# AppleMouse.net
KiCad netlist of a schematic drawn in EAGLE
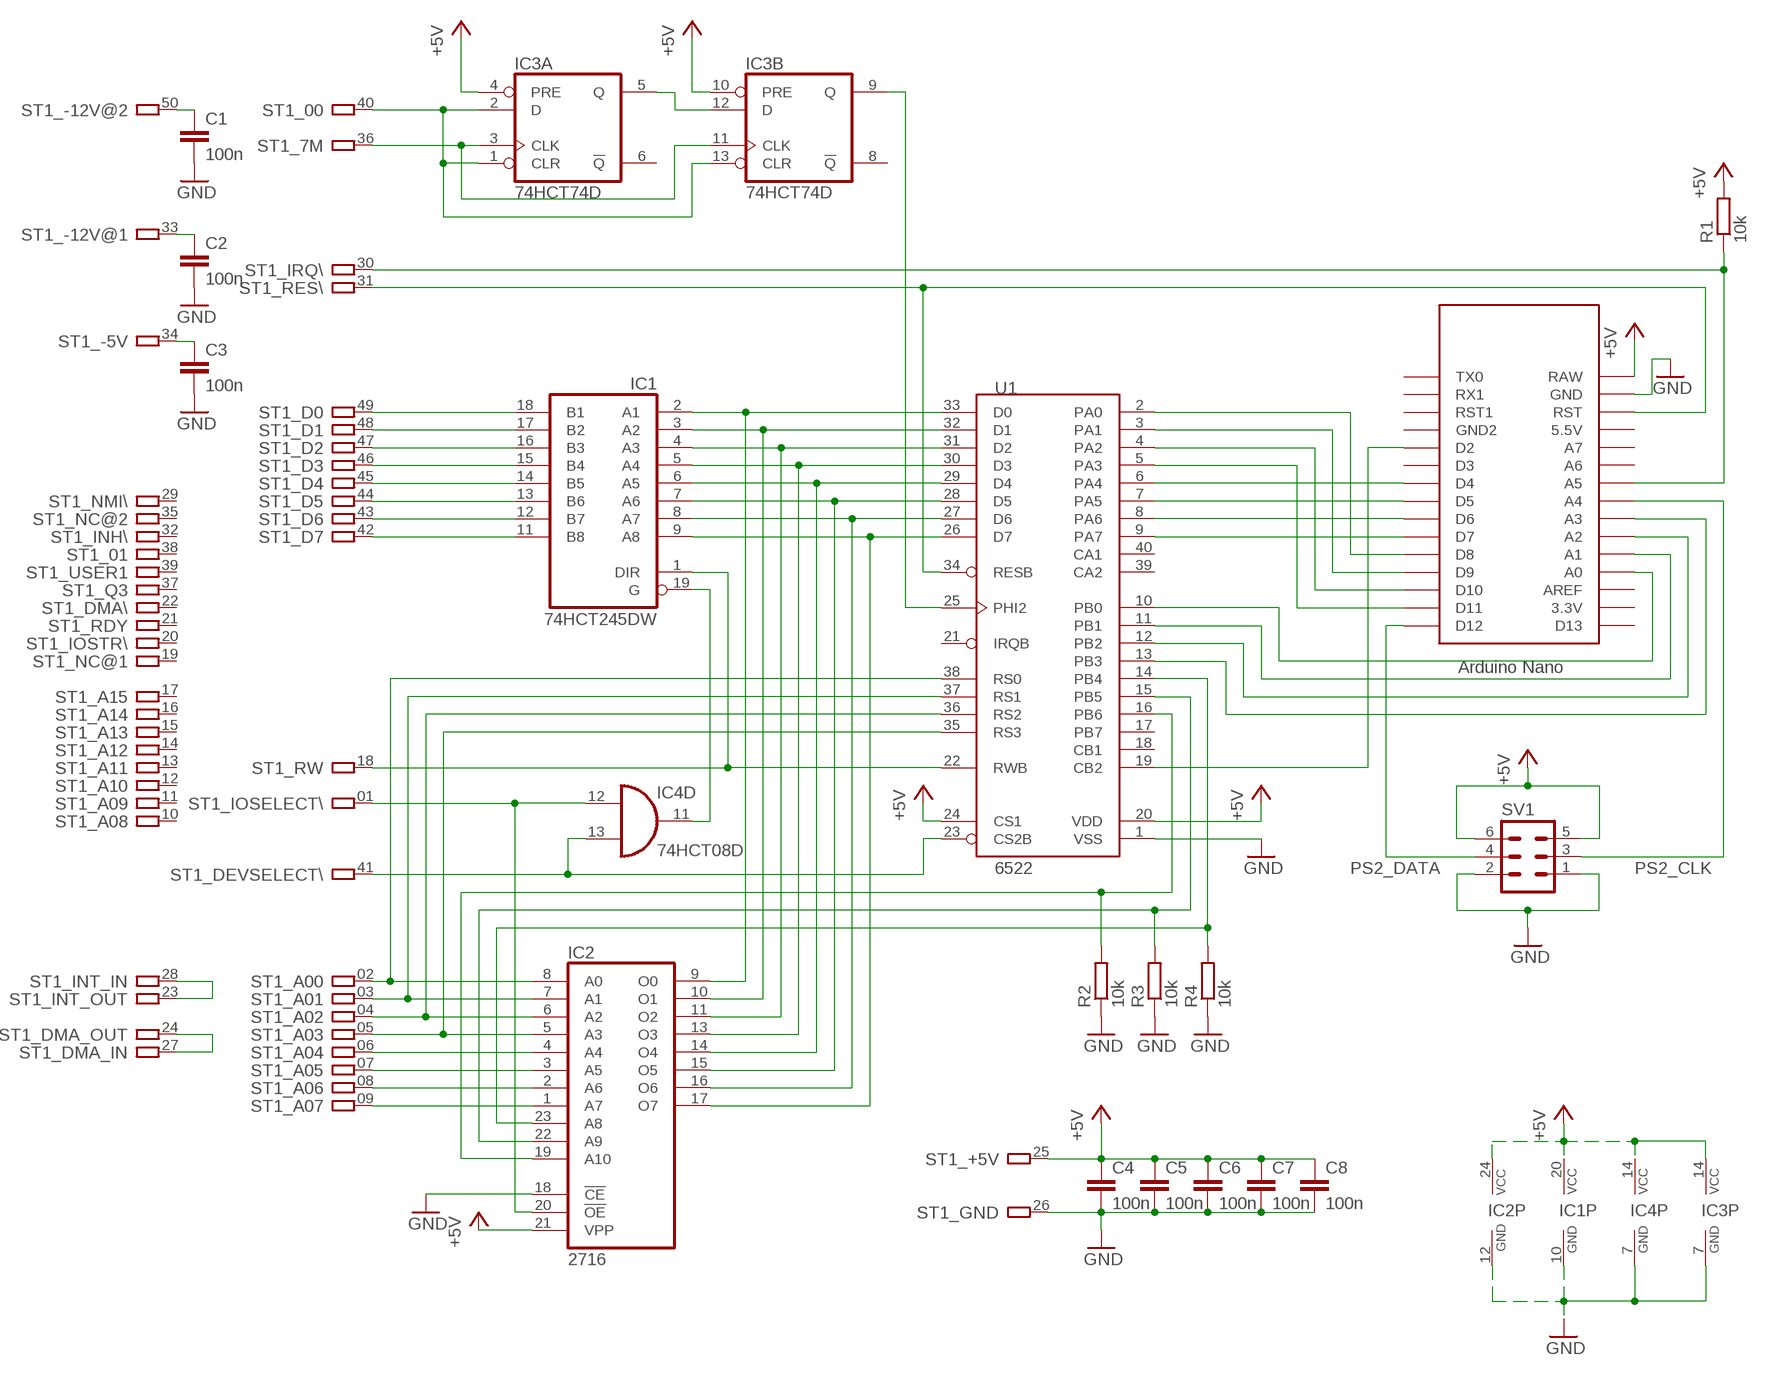
[diagram p0: schematic, sheet 1]

(export (version "E")
  (design (tool "Eeschema 10.0.6"))
  (components
    (comp (ref "C1")
      (value "100n")
      (footprint "eagle-import:C0805")
      (libsource (lib "eagle-import") (part "C-EUC0805"))
    )
    (comp (ref "C2")
      (value "100n")
      (footprint "eagle-import:C0805")
      (libsource (lib "eagle-import") (part "C-EUC0805"))
    )
    (comp (ref "C3")
      (value "100n")
      (footprint "eagle-import:C0805")
      (libsource (lib "eagle-import") (part "C-EUC0805"))
    )
    (comp (ref "C4")
      (value "100n")
      (footprint "eagle-import:C0805")
      (libsource (lib "eagle-import") (part "C-EUC0805"))
    )
    (comp (ref "C5")
      (value "100n")
      (footprint "eagle-import:C0805")
      (libsource (lib "eagle-import") (part "C-EUC0805"))
    )
    (comp (ref "C6")
      (value "100n")
      (footprint "eagle-import:C0805")
      (libsource (lib "eagle-import") (part "C-EUC0805"))
    )
    (comp (ref "C7")
      (value "100n")
      (footprint "eagle-import:C0805")
      (libsource (lib "eagle-import") (part "C-EUC0805"))
    )
    (comp (ref "C8")
      (value "100n")
      (footprint "eagle-import:C0805")
      (libsource (lib "eagle-import") (part "C-EUC0805"))
    )
    (comp (ref "IC1")
      (value "74HCT245DW")
      (footprint "eagle-import:SO20W")
      (libsource (lib "eagle-import") (part "74245DWHCT"))
    )
    (comp (ref "IC2")
      (value "2716")
      (footprint "eagle-import:DIL24")
      (libsource (lib "eagle-import") (part "2716"))
    )
    (comp (ref "IC3")
      (value "74HCT74D")
      (footprint "eagle-import:SO14")
      (libsource (lib "eagle-import") (part "7474DHCT"))
    )
    (comp (ref "IC4")
      (value "74HCT08D")
      (footprint "eagle-import:SO14")
      (libsource (lib "eagle-import") (part "7408DHCT"))
    )
    (comp (ref "R1")
      (value "10k")
      (footprint "eagle-import:R0805")
      (libsource (lib "eagle-import") (part "R-EU_R0805"))
    )
    (comp (ref "R2")
      (value "10k")
      (footprint "eagle-import:R0805")
      (libsource (lib "eagle-import") (part "R-EU_R0805"))
    )
    (comp (ref "R3")
      (value "10k")
      (footprint "eagle-import:R0805")
      (libsource (lib "eagle-import") (part "R-EU_R0805"))
    )
    (comp (ref "R4")
      (value "10k")
      (footprint "eagle-import:R0805")
      (libsource (lib "eagle-import") (part "R-EU_R0805"))
    )
    (comp (ref "ST1")
      (value "A2-50PINSLOT1-3")
      (footprint "eagle-import:A2-50PIN-SL1-3")
      (libsource (lib "eagle-import") (part "A2-50PINSLOT1-3"))
    )
    (comp (ref "SV1")
      (value "ML6")
      (footprint "eagle-import:ML6")
      (libsource (lib "eagle-import") (part "ML6"))
    )
    (comp (ref "U$1")
      (value "NANO")
      (footprint "eagle-import:NANO")
      (libsource (lib "eagle-import") (part "NANO"))
    )
    (comp (ref "U1")
      (value "6522")
      (footprint "eagle-import:DIP40")
      (libsource (lib "eagle-import") (part "W65C22DIP40"))
    )
  )
  (nets
    (net (code "1") (name "+5V") (class "Default")
      (node (ref "C4") (pin "1") (pinfunction "1_1") (pintype "passive"))
      (node (ref "C5") (pin "1") (pinfunction "1_1") (pintype "passive"))
      (node (ref "C6") (pin "1") (pinfunction "1_1") (pintype "passive"))
      (node (ref "C7") (pin "1") (pinfunction "1_1") (pintype "passive"))
      (node (ref "C8") (pin "1") (pinfunction "1_1") (pintype "passive"))
      (node (ref "IC1") (pin "20") (pinfunction "VCC_20") (pintype "power_in"))
      (node (ref "IC2") (pin "21") (pinfunction "VPP_21") (pintype "input"))
      (node (ref "IC2") (pin "24") (pinfunction "VCC_24") (pintype "power_in"))
      (node (ref "IC3") (pin "10") (pinfunction "PRE_10") (pintype "input"))
      (node (ref "IC3") (pin "14") (pinfunction "VCC_14") (pintype "power_in"))
      (node (ref "IC3") (pin "4") (pinfunction "PRE_4") (pintype "input"))
      (node (ref "IC4") (pin "14") (pinfunction "VCC_14") (pintype "power_in"))
      (node (ref "R1") (pin "2") (pinfunction "2_2") (pintype "passive"))
      (node (ref "ST1") (pin "25") (pinfunction "P_25") (pintype "bidirectional"))
      (node (ref "SV1") (pin "5") (pinfunction "5_5") (pintype "passive"))
      (node (ref "SV1") (pin "6") (pinfunction "6_6") (pintype "passive"))
      (node (ref "U$1") (pin "RAW") (pinfunction "RAW_RAW") (pintype "bidirectional"))
      (node (ref "U1") (pin "20") (pinfunction "VDD_20") (pintype "power_in"))
      (node (ref "U1") (pin "24") (pinfunction "CS1_24") (pintype "input"))
    )
    (net (code "2") (name "/PS2_CLK") (class "Default")
      (node (ref "SV1") (pin "3") (pinfunction "3_3") (pintype "passive"))
      (node (ref "U$1") (pin "A4") (pinfunction "A4_A4") (pintype "bidirectional"))
    )
    (net (code "3") (name "/PS2_DATA") (class "Default")
      (node (ref "SV1") (pin "4") (pinfunction "4_4") (pintype "passive"))
      (node (ref "U$1") (pin "D12") (pinfunction "D12_D12") (pintype "bidirectional"))
    )
    (net (code "4") (name "GND") (class "Default")
      (node (ref "C1") (pin "2") (pinfunction "2_2") (pintype "passive"))
      (node (ref "C2") (pin "2") (pinfunction "2_2") (pintype "passive"))
      (node (ref "C3") (pin "2") (pinfunction "2_2") (pintype "passive"))
      (node (ref "C4") (pin "2") (pinfunction "2_2") (pintype "passive"))
      (node (ref "C5") (pin "2") (pinfunction "2_2") (pintype "passive"))
      (node (ref "C6") (pin "2") (pinfunction "2_2") (pintype "passive"))
      (node (ref "C7") (pin "2") (pinfunction "2_2") (pintype "passive"))
      (node (ref "C8") (pin "2") (pinfunction "2_2") (pintype "passive"))
      (node (ref "IC1") (pin "10") (pinfunction "GND_10") (pintype "power_in"))
      (node (ref "IC2") (pin "12") (pinfunction "GND_12") (pintype "power_in"))
      (node (ref "IC2") (pin "18") (pinfunction "~{CE}_18") (pintype "input"))
      (node (ref "IC3") (pin "7") (pinfunction "GND_7") (pintype "power_in"))
      (node (ref "IC4") (pin "7") (pinfunction "GND_7") (pintype "power_in"))
      (node (ref "R2") (pin "1") (pinfunction "1_1") (pintype "passive"))
      (node (ref "R3") (pin "1") (pinfunction "1_1") (pintype "passive"))
      (node (ref "R4") (pin "1") (pinfunction "1_1") (pintype "passive"))
      (node (ref "ST1") (pin "26") (pinfunction "P_26") (pintype "bidirectional"))
      (node (ref "SV1") (pin "1") (pinfunction "1_1") (pintype "passive"))
      (node (ref "SV1") (pin "2") (pinfunction "2_2") (pintype "passive"))
      (node (ref "U$1") (pin "GND") (pinfunction "GND_GND") (pintype "bidirectional"))
      (node (ref "U1") (pin "1") (pinfunction "VSS_1") (pintype "power_in"))
    )
    (net (code "5") (name "Net-(IC1A-A1)") (class "Default")
      (node (ref "IC1") (pin "2") (pinfunction "A1_2") (pintype "bidirectional"))
      (node (ref "IC2") (pin "9") (pinfunction "O0_9") (pintype "tri_state"))
      (node (ref "U1") (pin "33") (pinfunction "D0_33") (pintype "bidirectional"))
    )
    (net (code "6") (name "Net-(IC1A-A2)") (class "Default")
      (node (ref "IC1") (pin "3") (pinfunction "A2_3") (pintype "bidirectional"))
      (node (ref "IC2") (pin "10") (pinfunction "O1_10") (pintype "tri_state"))
      (node (ref "U1") (pin "32") (pinfunction "D1_32") (pintype "bidirectional"))
    )
    (net (code "7") (name "Net-(IC1A-A3)") (class "Default")
      (node (ref "IC1") (pin "4") (pinfunction "A3_4") (pintype "bidirectional"))
      (node (ref "IC2") (pin "11") (pinfunction "O2_11") (pintype "tri_state"))
      (node (ref "U1") (pin "31") (pinfunction "D2_31") (pintype "bidirectional"))
    )
    (net (code "8") (name "Net-(IC1A-A4)") (class "Default")
      (node (ref "IC1") (pin "5") (pinfunction "A4_5") (pintype "bidirectional"))
      (node (ref "IC2") (pin "13") (pinfunction "O3_13") (pintype "tri_state"))
      (node (ref "U1") (pin "30") (pinfunction "D3_30") (pintype "bidirectional"))
    )
    (net (code "9") (name "Net-(IC1A-A5)") (class "Default")
      (node (ref "IC1") (pin "6") (pinfunction "A5_6") (pintype "bidirectional"))
      (node (ref "IC2") (pin "14") (pinfunction "O4_14") (pintype "tri_state"))
      (node (ref "U1") (pin "29") (pinfunction "D4_29") (pintype "bidirectional"))
    )
    (net (code "10") (name "Net-(IC1A-A6)") (class "Default")
      (node (ref "IC1") (pin "7") (pinfunction "A6_7") (pintype "bidirectional"))
      (node (ref "IC2") (pin "15") (pinfunction "O5_15") (pintype "tri_state"))
      (node (ref "U1") (pin "28") (pinfunction "D5_28") (pintype "bidirectional"))
    )
    (net (code "11") (name "Net-(IC1A-A7)") (class "Default")
      (node (ref "IC1") (pin "8") (pinfunction "A7_8") (pintype "bidirectional"))
      (node (ref "IC2") (pin "16") (pinfunction "O6_16") (pintype "tri_state"))
      (node (ref "U1") (pin "27") (pinfunction "D6_27") (pintype "bidirectional"))
    )
    (net (code "12") (name "Net-(IC1A-A8)") (class "Default")
      (node (ref "IC1") (pin "9") (pinfunction "A8_9") (pintype "bidirectional"))
      (node (ref "IC2") (pin "17") (pinfunction "O7_17") (pintype "tri_state"))
      (node (ref "U1") (pin "26") (pinfunction "D7_26") (pintype "bidirectional"))
    )
    (net (code "13") (name "Net-(IC1A-B1)") (class "Default")
      (node (ref "IC1") (pin "18") (pinfunction "B1_18") (pintype "bidirectional"))
      (node (ref "ST1") (pin "49") (pinfunction "P_49") (pintype "bidirectional"))
    )
    (net (code "14") (name "Net-(IC1A-B2)") (class "Default")
      (node (ref "IC1") (pin "17") (pinfunction "B2_17") (pintype "bidirectional"))
      (node (ref "ST1") (pin "48") (pinfunction "P_48") (pintype "bidirectional"))
    )
    (net (code "15") (name "Net-(IC1A-B3)") (class "Default")
      (node (ref "IC1") (pin "16") (pinfunction "B3_16") (pintype "bidirectional"))
      (node (ref "ST1") (pin "47") (pinfunction "P_47") (pintype "bidirectional"))
    )
    (net (code "16") (name "Net-(IC1A-B4)") (class "Default")
      (node (ref "IC1") (pin "15") (pinfunction "B4_15") (pintype "bidirectional"))
      (node (ref "ST1") (pin "46") (pinfunction "P_46") (pintype "bidirectional"))
    )
    (net (code "17") (name "Net-(IC1A-B5)") (class "Default")
      (node (ref "IC1") (pin "14") (pinfunction "B5_14") (pintype "bidirectional"))
      (node (ref "ST1") (pin "45") (pinfunction "P_45") (pintype "bidirectional"))
    )
    (net (code "18") (name "Net-(IC1A-B6)") (class "Default")
      (node (ref "IC1") (pin "13") (pinfunction "B6_13") (pintype "bidirectional"))
      (node (ref "ST1") (pin "44") (pinfunction "P_44") (pintype "bidirectional"))
    )
    (net (code "19") (name "Net-(IC1A-B7)") (class "Default")
      (node (ref "IC1") (pin "12") (pinfunction "B7_12") (pintype "bidirectional"))
      (node (ref "ST1") (pin "43") (pinfunction "P_43") (pintype "bidirectional"))
    )
    (net (code "20") (name "Net-(IC1A-B8)") (class "Default")
      (node (ref "IC1") (pin "11") (pinfunction "B8_11") (pintype "bidirectional"))
      (node (ref "ST1") (pin "42") (pinfunction "P_42") (pintype "bidirectional"))
    )
    (net (code "21") (name "Net-(IC1A-DIR)") (class "Default")
      (node (ref "IC1") (pin "1") (pinfunction "DIR_1") (pintype "input"))
      (node (ref "ST1") (pin "18") (pinfunction "P_18") (pintype "bidirectional"))
      (node (ref "U1") (pin "22") (pinfunction "RWB_22") (pintype "input"))
    )
    (net (code "22") (name "Net-(IC1A-G)") (class "Default")
      (node (ref "IC1") (pin "19") (pinfunction "G_19") (pintype "input"))
      (node (ref "IC4") (pin "11") (pinfunction "O_11") (pintype "output"))
    )
    (net (code "23") (name "Net-(IC2A-A0)") (class "Default")
      (node (ref "IC2") (pin "8") (pinfunction "A0_8") (pintype "input"))
      (node (ref "ST1") (pin "02") (pinfunction "P_02") (pintype "bidirectional"))
      (node (ref "U1") (pin "38") (pinfunction "RS0_38") (pintype "input"))
    )
    (net (code "24") (name "Net-(IC2A-A1)") (class "Default")
      (node (ref "IC2") (pin "7") (pinfunction "A1_7") (pintype "input"))
      (node (ref "ST1") (pin "03") (pinfunction "P_03") (pintype "bidirectional"))
      (node (ref "U1") (pin "37") (pinfunction "RS1_37") (pintype "input"))
    )
    (net (code "25") (name "Net-(IC2A-A2)") (class "Default")
      (node (ref "IC2") (pin "6") (pinfunction "A2_6") (pintype "input"))
      (node (ref "ST1") (pin "04") (pinfunction "P_04") (pintype "bidirectional"))
      (node (ref "U1") (pin "36") (pinfunction "RS2_36") (pintype "input"))
    )
    (net (code "26") (name "Net-(IC2A-A3)") (class "Default")
      (node (ref "IC2") (pin "5") (pinfunction "A3_5") (pintype "input"))
      (node (ref "ST1") (pin "05") (pinfunction "P_05") (pintype "bidirectional"))
      (node (ref "U1") (pin "35") (pinfunction "RS3_35") (pintype "input"))
    )
    (net (code "27") (name "Net-(IC2A-A4)") (class "Default")
      (node (ref "IC2") (pin "4") (pinfunction "A4_4") (pintype "input"))
      (node (ref "ST1") (pin "06") (pinfunction "P_06") (pintype "bidirectional"))
    )
    (net (code "28") (name "Net-(IC2A-A5)") (class "Default")
      (node (ref "IC2") (pin "3") (pinfunction "A5_3") (pintype "input"))
      (node (ref "ST1") (pin "07") (pinfunction "P_07") (pintype "bidirectional"))
    )
    (net (code "29") (name "Net-(IC2A-A6)") (class "Default")
      (node (ref "IC2") (pin "2") (pinfunction "A6_2") (pintype "input"))
      (node (ref "ST1") (pin "08") (pinfunction "P_08") (pintype "bidirectional"))
    )
    (net (code "30") (name "Net-(IC2A-A7)") (class "Default")
      (node (ref "IC2") (pin "1") (pinfunction "A7_1") (pintype "input"))
      (node (ref "ST1") (pin "09") (pinfunction "P_09") (pintype "bidirectional"))
    )
    (net (code "31") (name "Net-(IC2A-A8)") (class "Default")
      (node (ref "IC2") (pin "23") (pinfunction "A8_23") (pintype "input"))
      (node (ref "R4") (pin "2") (pinfunction "2_2") (pintype "passive"))
      (node (ref "U1") (pin "14") (pinfunction "PB4_14") (pintype "bidirectional"))
    )
    (net (code "32") (name "Net-(IC2A-A9)") (class "Default")
      (node (ref "IC2") (pin "22") (pinfunction "A9_22") (pintype "input"))
      (node (ref "R3") (pin "2") (pinfunction "2_2") (pintype "passive"))
      (node (ref "U1") (pin "15") (pinfunction "PB5_15") (pintype "bidirectional"))
    )
    (net (code "33") (name "Net-(IC2A-A10)") (class "Default")
      (node (ref "IC2") (pin "19") (pinfunction "A10_19") (pintype "input"))
      (node (ref "R2") (pin "2") (pinfunction "2_2") (pintype "passive"))
      (node (ref "U1") (pin "16") (pinfunction "PB6_16") (pintype "bidirectional"))
    )
    (net (code "34") (name "Net-(IC2A-~{OE})") (class "Default")
      (node (ref "IC2") (pin "20") (pinfunction "~{OE}_20") (pintype "input"))
      (node (ref "IC4") (pin "12") (pinfunction "I0_12") (pintype "input"))
      (node (ref "ST1") (pin "01") (pinfunction "P_01") (pintype "bidirectional"))
    )
    (net (code "35") (name "Net-(IC3A-CLK)") (class "Default")
      (node (ref "IC3") (pin "11") (pinfunction "CLK_11") (pintype "input"))
      (node (ref "IC3") (pin "3") (pinfunction "CLK_3") (pintype "input"))
      (node (ref "ST1") (pin "36") (pinfunction "P_36") (pintype "bidirectional"))
    )
    (net (code "36") (name "Net-(IC3A-CLR)") (class "Default")
      (node (ref "IC3") (pin "1") (pinfunction "CLR_1") (pintype "input"))
      (node (ref "IC3") (pin "13") (pinfunction "CLR_13") (pintype "input"))
      (node (ref "IC3") (pin "2") (pinfunction "D_2") (pintype "input"))
      (node (ref "ST1") (pin "40") (pinfunction "P_40") (pintype "bidirectional"))
    )
    (net (code "37") (name "Net-(IC3A-Q)") (class "Default")
      (node (ref "IC3") (pin "12") (pinfunction "D_12") (pintype "input"))
      (node (ref "IC3") (pin "5") (pinfunction "Q_5") (pintype "output"))
    )
    (net (code "38") (name "Net-(IC3B-Q)") (class "Default")
      (node (ref "IC3") (pin "9") (pinfunction "Q_9") (pintype "output"))
      (node (ref "U1") (pin "25") (pinfunction "PHI2_25") (pintype "input"))
    )
    (net (code "39") (name "Net-(IC4D-I1)") (class "Default")
      (node (ref "IC4") (pin "13") (pinfunction "I1_13") (pintype "input"))
      (node (ref "ST1") (pin "41") (pinfunction "P_41") (pintype "bidirectional"))
      (node (ref "U1") (pin "23") (pinfunction "CS2B_23") (pintype "input"))
    )
    (net (code "40") (name "Net-(ST1AH-P)") (class "Default")
      (node (ref "ST1") (pin "24") (pinfunction "P_24") (pintype "bidirectional"))
      (node (ref "ST1") (pin "27") (pinfunction "P_27") (pintype "bidirectional"))
    )
    (net (code "41") (name "Net-(ST1AL-P)") (class "Default")
      (node (ref "ST1") (pin "23") (pinfunction "P_23") (pintype "bidirectional"))
      (node (ref "ST1") (pin "28") (pinfunction "P_28") (pintype "bidirectional"))
    )
    (net (code "42") (name "Net-(ST1AP-P)") (class "Default")
      (node (ref "R1") (pin "1") (pinfunction "1_1") (pintype "passive"))
      (node (ref "ST1") (pin "30") (pinfunction "P_30") (pintype "bidirectional"))
      (node (ref "U$1") (pin "A5") (pinfunction "A5_A5") (pintype "bidirectional"))
    )
    (net (code "43") (name "Net-(ST1AV-P)") (class "Default")
      (node (ref "ST1") (pin "31") (pinfunction "P_31") (pintype "bidirectional"))
      (node (ref "U$1") (pin "RST") (pinfunction "RST_RST") (pintype "bidirectional"))
      (node (ref "U1") (pin "34") (pinfunction "RESB_34") (pintype "input"))
    )
    (net (code "44") (name "Net-(ST1B-P)") (class "Default")
      (node (ref "C2") (pin "1") (pinfunction "1_1") (pintype "passive"))
      (node (ref "ST1") (pin "33") (pinfunction "P_33") (pintype "bidirectional"))
    )
    (net (code "45") (name "Net-(ST1C-P)") (class "Default")
      (node (ref "C1") (pin "1") (pinfunction "1_1") (pintype "passive"))
      (node (ref "ST1") (pin "50") (pinfunction "P_50") (pintype "bidirectional"))
    )
    (net (code "46") (name "Net-(ST1D-P)") (class "Default")
      (node (ref "C3") (pin "1") (pinfunction "1_1") (pintype "passive"))
      (node (ref "ST1") (pin "34") (pinfunction "P_34") (pintype "bidirectional"))
    )
    (net (code "47") (name "Net-(U1-CB2)") (class "Default")
      (node (ref "U$1") (pin "D2") (pinfunction "D2_D2") (pintype "bidirectional"))
      (node (ref "U1") (pin "19") (pinfunction "CB2_19") (pintype "bidirectional"))
    )
    (net (code "48") (name "Net-(U1-PA0)") (class "Default")
      (node (ref "U$1") (pin "D8") (pinfunction "D8_D8") (pintype "bidirectional"))
      (node (ref "U1") (pin "2") (pinfunction "PA0_2") (pintype "bidirectional"))
    )
    (net (code "49") (name "Net-(U1-PA1)") (class "Default")
      (node (ref "U$1") (pin "D9") (pinfunction "D9_D9") (pintype "bidirectional"))
      (node (ref "U1") (pin "3") (pinfunction "PA1_3") (pintype "bidirectional"))
    )
    (net (code "50") (name "Net-(U1-PA2)") (class "Default")
      (node (ref "U$1") (pin "D10") (pinfunction "D10_D10") (pintype "bidirectional"))
      (node (ref "U1") (pin "4") (pinfunction "PA2_4") (pintype "bidirectional"))
    )
    (net (code "51") (name "Net-(U1-PA3)") (class "Default")
      (node (ref "U$1") (pin "D11") (pinfunction "D11_D11") (pintype "bidirectional"))
      (node (ref "U1") (pin "5") (pinfunction "PA3_5") (pintype "bidirectional"))
    )
    (net (code "52") (name "Net-(U1-PA4)") (class "Default")
      (node (ref "U$1") (pin "D4") (pinfunction "D4_D4") (pintype "bidirectional"))
      (node (ref "U1") (pin "6") (pinfunction "PA4_6") (pintype "bidirectional"))
    )
    (net (code "53") (name "Net-(U1-PA5)") (class "Default")
      (node (ref "U$1") (pin "D5") (pinfunction "D5_D5") (pintype "bidirectional"))
      (node (ref "U1") (pin "7") (pinfunction "PA5_7") (pintype "bidirectional"))
    )
    (net (code "54") (name "Net-(U1-PA6)") (class "Default")
      (node (ref "U$1") (pin "D6") (pinfunction "D6_D6") (pintype "bidirectional"))
      (node (ref "U1") (pin "8") (pinfunction "PA6_8") (pintype "bidirectional"))
    )
    (net (code "55") (name "Net-(U1-PA7)") (class "Default")
      (node (ref "U$1") (pin "D7") (pinfunction "D7_D7") (pintype "bidirectional"))
      (node (ref "U1") (pin "9") (pinfunction "PA7_9") (pintype "bidirectional"))
    )
    (net (code "56") (name "Net-(U1-PB0)") (class "Default")
      (node (ref "U$1") (pin "A0") (pinfunction "A0_A0") (pintype "bidirectional"))
      (node (ref "U1") (pin "10") (pinfunction "PB0_10") (pintype "bidirectional"))
    )
    (net (code "57") (name "Net-(U1-PB1)") (class "Default")
      (node (ref "U$1") (pin "A1") (pinfunction "A1_A1") (pintype "bidirectional"))
      (node (ref "U1") (pin "11") (pinfunction "PB1_11") (pintype "bidirectional"))
    )
    (net (code "58") (name "Net-(U1-PB2)") (class "Default")
      (node (ref "U$1") (pin "A2") (pinfunction "A2_A2") (pintype "bidirectional"))
      (node (ref "U1") (pin "12") (pinfunction "PB2_12") (pintype "bidirectional"))
    )
    (net (code "59") (name "Net-(U1-PB3)") (class "Default")
      (node (ref "U$1") (pin "A3") (pinfunction "A3_A3") (pintype "bidirectional"))
      (node (ref "U1") (pin "13") (pinfunction "PB3_13") (pintype "bidirectional"))
    )
    (net (code "60") (name "unconnected-(IC3A-~{Q}-Pad6)") (class "Default")
      (node (ref "IC3") (pin "6") (pinfunction "~{Q}_6") (pintype "output"))
    )
    (net (code "61") (name "unconnected-(IC3B-~{Q}-Pad8)") (class "Default")
      (node (ref "IC3") (pin "8") (pinfunction "~{Q}_8") (pintype "output"))
    )
    (net (code "62") (name "unconnected-(ST1AG-P-Pad22)") (class "Default")
      (node (ref "ST1") (pin "22") (pinfunction "P_22") (pintype "bidirectional"))
    )
    (net (code "63") (name "unconnected-(ST1AK-P-Pad32)") (class "Default")
      (node (ref "ST1") (pin "32") (pinfunction "P_32") (pintype "bidirectional"))
    )
    (net (code "64") (name "unconnected-(ST1AO-P-Pad20)") (class "Default")
      (node (ref "ST1") (pin "20") (pinfunction "P_20") (pintype "bidirectional"))
    )
    (net (code "65") (name "unconnected-(ST1AQ-P-Pad19)") (class "Default")
      (node (ref "ST1") (pin "19") (pinfunction "P_19") (pintype "bidirectional"))
    )
    (net (code "66") (name "unconnected-(ST1AR-P-Pad35)") (class "Default")
      (node (ref "ST1") (pin "35") (pinfunction "P_35") (pintype "bidirectional"))
    )
    (net (code "67") (name "unconnected-(ST1AS-P-Pad29)") (class "Default")
      (node (ref "ST1") (pin "29") (pinfunction "P_29") (pintype "bidirectional"))
    )
    (net (code "68") (name "unconnected-(ST1AT-P-Pad37)") (class "Default")
      (node (ref "ST1") (pin "37") (pinfunction "P_37") (pintype "bidirectional"))
    )
    (net (code "69") (name "unconnected-(ST1AU-P-Pad21)") (class "Default")
      (node (ref "ST1") (pin "21") (pinfunction "P_21") (pintype "bidirectional"))
    )
    (net (code "70") (name "unconnected-(ST1AX-P-Pad39)") (class "Default")
      (node (ref "ST1") (pin "39") (pinfunction "P_39") (pintype "bidirectional"))
    )
    (net (code "71") (name "unconnected-(ST1F-P-Pad38)") (class "Default")
      (node (ref "ST1") (pin "38") (pinfunction "P_38") (pintype "bidirectional"))
    )
    (net (code "72") (name "unconnected-(ST1P-P-Pad10)") (class "Default")
      (node (ref "ST1") (pin "10") (pinfunction "P_10") (pintype "bidirectional"))
    )
    (net (code "73") (name "unconnected-(ST1Q-P-Pad11)") (class "Default")
      (node (ref "ST1") (pin "11") (pinfunction "P_11") (pintype "bidirectional"))
    )
    (net (code "74") (name "unconnected-(ST1R-P-Pad12)") (class "Default")
      (node (ref "ST1") (pin "12") (pinfunction "P_12") (pintype "bidirectional"))
    )
    (net (code "75") (name "unconnected-(ST1S-P-Pad13)") (class "Default")
      (node (ref "ST1") (pin "13") (pinfunction "P_13") (pintype "bidirectional"))
    )
    (net (code "76") (name "unconnected-(ST1T-P-Pad14)") (class "Default")
      (node (ref "ST1") (pin "14") (pinfunction "P_14") (pintype "bidirectional"))
    )
    (net (code "77") (name "unconnected-(ST1U-P-Pad15)") (class "Default")
      (node (ref "ST1") (pin "15") (pinfunction "P_15") (pintype "bidirectional"))
    )
    (net (code "78") (name "unconnected-(ST1V-P-Pad16)") (class "Default")
      (node (ref "ST1") (pin "16") (pinfunction "P_16") (pintype "bidirectional"))
    )
    (net (code "79") (name "unconnected-(ST1W-P-Pad17)") (class "Default")
      (node (ref "ST1") (pin "17") (pinfunction "P_17") (pintype "bidirectional"))
    )
    (net (code "80") (name "unconnected-(U$1-5.5V-Pad5V)") (class "Default")
      (node (ref "U$1") (pin "5V") (pinfunction "5.5V_5V") (pintype "bidirectional"))
    )
    (net (code "81") (name "unconnected-(U$1-GND2-PadGND1)") (class "Default")
      (node (ref "U$1") (pin "GND1") (pinfunction "GND2_GND1") (pintype "bidirectional"))
    )
    (net (code "82") (name "unconnected-(U$1-Pad3.3V)") (class "Default")
      (node (ref "U$1") (pin "3.3V") (pinfunction "3.3V_3.3V") (pintype "bidirectional"))
    )
    (net (code "83") (name "unconnected-(U$1-PadA6)") (class "Default")
      (node (ref "U$1") (pin "A6") (pinfunction "A6_A6") (pintype "bidirectional"))
    )
    (net (code "84") (name "unconnected-(U$1-PadA7)") (class "Default")
      (node (ref "U$1") (pin "A7") (pinfunction "A7_A7") (pintype "bidirectional"))
    )
    (net (code "85") (name "unconnected-(U$1-PadAREF)") (class "Default")
      (node (ref "U$1") (pin "AREF") (pinfunction "AREF_AREF") (pintype "bidirectional"))
    )
    (net (code "86") (name "unconnected-(U$1-PadD3)") (class "Default")
      (node (ref "U$1") (pin "D3") (pinfunction "D3_D3") (pintype "bidirectional"))
    )
    (net (code "87") (name "unconnected-(U$1-PadD13)") (class "Default")
      (node (ref "U$1") (pin "D13") (pinfunction "D13_D13") (pintype "bidirectional"))
    )
    (net (code "88") (name "unconnected-(U$1-PadICSP1)") (class "Default")
      (node (ref "U$1") (pin "ICSP1") (pinfunction "ICSP1_ICSP1") (pintype "bidirectional"))
    )
    (net (code "89") (name "unconnected-(U$1-PadICSP2)") (class "Default")
      (node (ref "U$1") (pin "ICSP2") (pinfunction "ICSP2_ICSP2") (pintype "bidirectional"))
    )
    (net (code "90") (name "unconnected-(U$1-PadICSP3)") (class "Default")
      (node (ref "U$1") (pin "ICSP3") (pinfunction "ICSP3_ICSP3") (pintype "bidirectional"))
    )
    (net (code "91") (name "unconnected-(U$1-PadICSP4)") (class "Default")
      (node (ref "U$1") (pin "ICSP4") (pinfunction "ICSP4_ICSP4") (pintype "bidirectional"))
    )
    (net (code "92") (name "unconnected-(U$1-PadICSP5)") (class "Default")
      (node (ref "U$1") (pin "ICSP5") (pinfunction "ICSP5_ICSP5") (pintype "bidirectional"))
    )
    (net (code "93") (name "unconnected-(U$1-PadICSP6)") (class "Default")
      (node (ref "U$1") (pin "ICSP6") (pinfunction "ICSP6_ICSP6") (pintype "bidirectional"))
    )
    (net (code "94") (name "unconnected-(U$1-PadRST1)") (class "Default")
      (node (ref "U$1") (pin "RST1") (pinfunction "RST1_RST1") (pintype "bidirectional"))
    )
    (net (code "95") (name "unconnected-(U$1-PadRX1)") (class "Default")
      (node (ref "U$1") (pin "RX1") (pinfunction "RX1_RX1") (pintype "bidirectional"))
    )
    (net (code "96") (name "unconnected-(U$1-PadTX0)") (class "Default")
      (node (ref "U$1") (pin "TX0") (pinfunction "TX0_TX0") (pintype "bidirectional"))
    )
    (net (code "97") (name "unconnected-(U1-CA1-Pad40)") (class "Default")
      (node (ref "U1") (pin "40") (pinfunction "CA1_40") (pintype "input"))
    )
    (net (code "98") (name "unconnected-(U1-CA2-Pad39)") (class "Default")
      (node (ref "U1") (pin "39") (pinfunction "CA2_39") (pintype "bidirectional"))
    )
    (net (code "99") (name "unconnected-(U1-CB1-Pad18)") (class "Default")
      (node (ref "U1") (pin "18") (pinfunction "CB1_18") (pintype "input"))
    )
    (net (code "100") (name "unconnected-(U1-IRQB-Pad21)") (class "Default")
      (node (ref "U1") (pin "21") (pinfunction "IRQB_21") (pintype "open_collector"))
    )
    (net (code "101") (name "unconnected-(U1-PB7-Pad17)") (class "Default")
      (node (ref "U1") (pin "17") (pinfunction "PB7_17") (pintype "bidirectional"))
    )
  )
)
